# Sensor_Board.net
KiCad netlist of a schematic drawn in Altium Designer
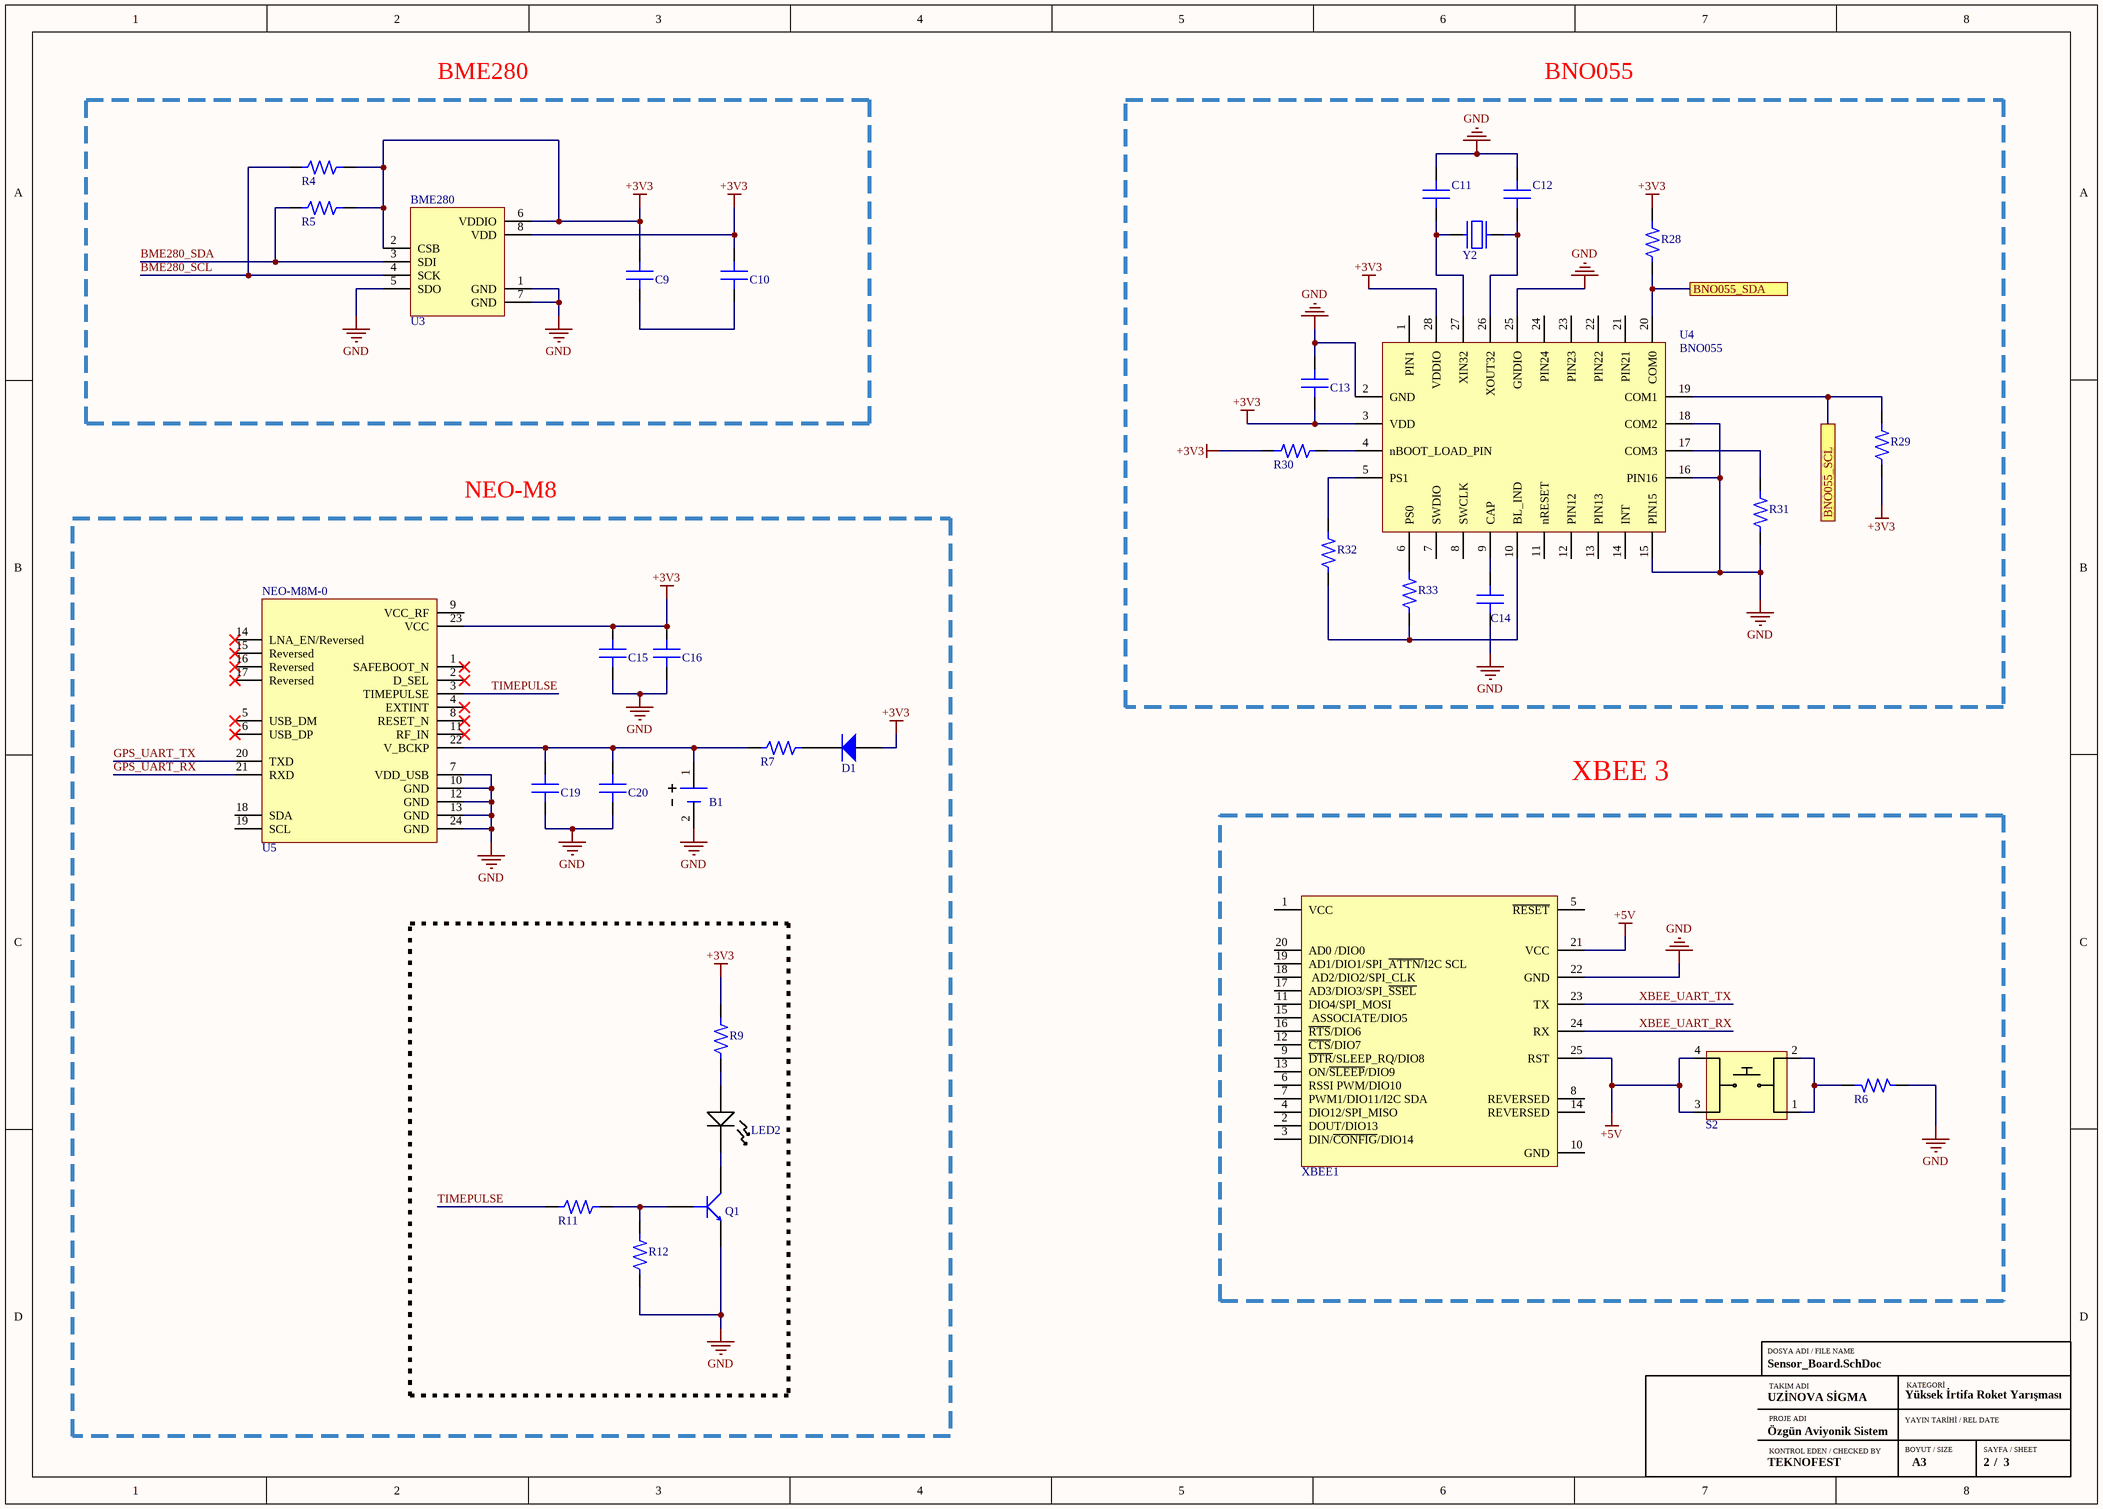
[diagram p0: Sensor_Board.SchDoc]

(export (version "E")
  (design (tool "Eeschema 10.0.6"))
  (components
    (comp (ref "B1")
      (value "MS920SE-FL27E")
      (footprint "MS920SE_Battery")
      (description "Lithium Battery Coin 3V 11mAh Rechargeable Tray")
      (fields (field (name "MANUFACTURER") "Epson") (field (name "VOLTAGE") "3V"))
      (libsource (lib "ROKET_LIBRARY") (part "BATTERY"))
    )
    (comp (ref "C9")
      (value "CAP CER 100nF 0805")
      (footprint "CAP_0805")
      (libsource (lib "ROKET_LIBRARY") (part "CAP CER 100nF 0805"))
    )
    (comp (ref "C10")
      (value "CAP CER 100nF 0805")
      (footprint "CAP_0805")
      (libsource (lib "ROKET_LIBRARY") (part "CAP CER 100nF 0805"))
    )
    (comp (ref "C11")
      (value "CAP CER 22pF 0805")
      (footprint "CAP_0805")
      (libsource (lib "Roket_Library") (part "CAP CER 22pF 0805"))
    )
    (comp (ref "C12")
      (value "CAP CER 22pF 0805")
      (footprint "CAP_0805")
      (libsource (lib "Roket_Library") (part "CAP CER 22pF 0805"))
    )
    (comp (ref "C13")
      (value "CAP CER 100nF 0805")
      (footprint "CAP_0805")
      (libsource (lib "ROKET_LIBRARY") (part "CAP CER 100nF 0805"))
    )
    (comp (ref "C14")
      (value "CAP CER 1uF 0805")
      (footprint "CAP_0805")
      (libsource (lib "ROKET_LIBRARY") (part "CAP CER 1uF 0805"))
    )
    (comp (ref "C15")
      (value "CAP CER 10uF 0805")
      (footprint "CAP_0805")
      (libsource (lib "ROKET_LIBRARY") (part "CAP CER 10uF 0805"))
    )
    (comp (ref "C16")
      (value "CAP CER 100nF 0805")
      (footprint "CAP_0805")
      (libsource (lib "ROKET_LIBRARY") (part "CAP CER 100nF 0805"))
    )
    (comp (ref "C19")
      (value "CAP CER 4.7uF 0805")
      (footprint "CAP_0805")
      (libsource (lib "ROKET_LIBRARY") (part "CAP CER 4.7uF 0805"))
    )
    (comp (ref "C20")
      (value "CAP CER 100nF 0805")
      (footprint "CAP_0805")
      (libsource (lib "ROKET_LIBRARY") (part "CAP CER 100nF 0805"))
    )
    (comp (ref "D1")
      (value "DIODE GEN PURP 75V 150MA SOD323F")
      (footprint "SOD323F")
      (description "VR=75V IF=150mA Trr=4ns P=200mW")
      (fields
        (field (name "MANUFACTURER") "ON Semiconductor / Fairchild")
        (field (name "MANUFACTURER PART NUMBER") "1N4148WS")
      )
      (libsource (lib "ROKET_LIBRARY") (part "DIODE"))
    )
    (comp (ref "LED2")
      (value "CMD17-21VRD/TR8")
      (footprint "LED RED_0805")
      (description "LED Uni-Color Red 640nm 2-Pin SMT T/R")
      (fields (field (name "MANUFACTURER") "VCC CHML"))
      (libsource (lib "ROKET_LIBRARY") (part "LED RED"))
    )
    (comp (ref "Q1")
      (value "MMBT3904-7-F")
      (footprint "SOT_23F")
      (description "NPN Ic=200mA Vceo=40V hfe=100~300 fT=310MHz P=300mW SOT-23")
      (fields (field (name "MANUFACTURER") "Diodes Zetex"))
      (libsource (lib "ROKET_LIBRARY") (part "BJT_NPN"))
    )
    (comp (ref "R4")
      (value "RES 4.7K OHM 0805")
      (footprint "RES_0805")
      (libsource (lib "ROKET_LIBRARY") (part "RES 4.7K OHM 0805"))
    )
    (comp (ref "R5")
      (value "RES 4.7K OHM 0805")
      (footprint "RES_0805")
      (libsource (lib "ROKET_LIBRARY") (part "RES 4.7K OHM 0805"))
    )
    (comp (ref "R6")
      (value "RES 10K OHM 0805")
      (footprint "RES_0805")
      (libsource (lib "ROKET_LIBRARY") (part "RES 10K OHM 0805"))
    )
    (comp (ref "R7")
      (value "RES 1K OHM 0805")
      (footprint "RES_0805")
      (libsource (lib "ROKET_LIBRARY") (part "RES 1K OHM 0805"))
    )
    (comp (ref "R9")
      (value "RES 1K OHM 0805")
      (footprint "RES_0805")
      (libsource (lib "ROKET_LIBRARY") (part "RES 1K OHM 0805"))
    )
    (comp (ref "R11")
      (value "RES 10K OHM 0805")
      (footprint "RES_0805")
      (libsource (lib "ROKET_LIBRARY") (part "RES 10K OHM 0805"))
    )
    (comp (ref "R12")
      (value "RES 10K OHM 0805")
      (footprint "RES_0805")
      (libsource (lib "ROKET_LIBRARY") (part "RES 10K OHM 0805"))
    )
    (comp (ref "R28")
      (value "RES 10K OHM 0805")
      (footprint "RES_0805")
      (libsource (lib "ROKET_LIBRARY") (part "RES 10K OHM 0805"))
    )
    (comp (ref "R29")
      (value "RES 10K OHM 0805")
      (footprint "RES_0805")
      (libsource (lib "ROKET_LIBRARY") (part "RES 10K OHM 0805"))
    )
    (comp (ref "R30")
      (value "RES 10K OHM 0805")
      (footprint "RES_0805")
      (libsource (lib "ROKET_LIBRARY") (part "RES 10K OHM 0805"))
    )
    (comp (ref "R31")
      (value "RES 10K OHM 0805")
      (footprint "RES_0805")
      (libsource (lib "ROKET_LIBRARY") (part "RES 10K OHM 0805"))
    )
    (comp (ref "R32")
      (value "RES 10K OHM 0805")
      (footprint "RES_0805")
      (libsource (lib "ROKET_LIBRARY") (part "RES 10K OHM 0805"))
    )
    (comp (ref "R33")
      (value "RES 10K OHM 0805")
      (footprint "RES_0805")
      (libsource (lib "ROKET_LIBRARY") (part "RES 10K OHM 0805"))
    )
    (comp (ref "S2")
      (value "PTS815 SJG 250 SMTR LFS")
      (footprint "BUTTON")
      (description "Switch Tactile N.O. SPST Button J-Bend 0.05A 12VDC 3.92N SMD T/R")
      (fields
        (field (name "MANUFACTURER") "ITT C&K")
        (field (name "MANUFACTURER PART NUMBER") "PTS815SJG250SMTRLFS")
      )
      (libsource (lib "ROKET_LIBRARY") (part "BUTTON"))
    )
    (comp (ref "U3")
      (value "BME280")
      (footprint "BME280")
      (description "Pressure, Temperature and Humidity Sensor Digital Output 1.8V 8-Pin LGA T/R")
      (fields (field (name "MANUFACTURER") "Bosch Tools"))
      (libsource (lib "ROKET_LIBRARY") (part "BME280"))
    )
    (comp (ref "U4")
      (value "BNO055")
      (footprint "BNO055")
      (description "BNO055 Series 1.7 to 3.6 V Intelligent 9-Axis Absolute Orientation Sensor-LGA-28")
      (fields (field (name "MANUFACTURER") "Bosch"))
      (libsource (lib "ROKET_LIBRARY") (part "BNO055"))
    )
    (comp (ref "U5")
      (value "NEO-M8M-0")
      (footprint "NEO-M8-GPS")
      (description "Rf Rcvr Gnss/gps 1.575GHZ 24LCC")
      (fields (field (name "MANUFACTURER") "u-blox"))
      (libsource (lib "ROKET_LIBRARY") (part "NEO-M8"))
    )
    (comp (ref "XBEE1")
      (value "XB3-24Z8ST-J")
      (footprint "XBEE3")
      (description "Zigbee Module, 2.4 Ghz, Sma Ant, Th Mt Rohs Compliant: Yes")
      (fields (field (name "MANUFACTURER") "Digi International"))
      (libsource (lib "Roket_Library") (part "XBEE3"))
    )
    (comp (ref "Y2")
      (value "CRYSTAL 32.7680KHZ 12.5PF SMD")
      (footprint "CRYSTAL_ABS05")
      (description "Crystal 0.032768MHz ±20ppm (Tol) 12.5pF Flexural 90000Ohm 2-Pin CSMD T/R")
      (fields
        (field (name "MANUFACTURER") "Abracon")
        (field (name "MANUFACTURER PART NUMBER") "ABS05-32.768KHZ-T")
      )
      (libsource (lib "ROKET_LIBRARY") (part "CRYSTAL"))
    )
  )
  (nets
    (net (code "1") (name "+3V3") (class "Default")
      (node (ref "C10") (pin "2") (pinfunction "2_2") (pintype "passive"))
      (node (ref "C13") (pin "1") (pinfunction "1_1") (pintype "passive"))
      (node (ref "C15") (pin "2") (pinfunction "2_2") (pintype "passive"))
      (node (ref "C16") (pin "2") (pinfunction "2_2") (pintype "passive"))
      (node (ref "C9") (pin "2") (pinfunction "2_2") (pintype "passive"))
      (node (ref "D1") (pin "2") (pinfunction "ANODE_2") (pintype "passive"))
      (node (ref "R28") (pin "2") (pinfunction "2_2") (pintype "passive"))
      (node (ref "R29") (pin "1") (pinfunction "1_1") (pintype "passive"))
      (node (ref "R30") (pin "2") (pinfunction "2_2") (pintype "passive"))
      (node (ref "R4") (pin "2") (pinfunction "2_2") (pintype "passive"))
      (node (ref "R5") (pin "2") (pinfunction "2_2") (pintype "passive"))
      (node (ref "R9") (pin "2") (pinfunction "2_2") (pintype "passive"))
      (node (ref "U3") (pin "2") (pinfunction "CSB_2") (pintype "passive"))
      (node (ref "U3") (pin "6") (pinfunction "VDDIO_6") (pintype "passive"))
      (node (ref "U3") (pin "8") (pinfunction "VDD_8") (pintype "passive"))
      (node (ref "U4") (pin "28") (pinfunction "VDDIO_28") (pintype "passive"))
      (node (ref "U4") (pin "3") (pinfunction "VDD_3") (pintype "passive"))
      (node (ref "U5") (pin "23") (pinfunction "VCC_23") (pintype "passive"))
    )
    (net (code "2") (name "+5V") (class "Default")
      (node (ref "S2") (pin "3") (pinfunction "3_3") (pintype "passive"))
      (node (ref "S2") (pin "4") (pinfunction "4_4") (pintype "passive"))
      (node (ref "XBEE1") (pin "21") (pinfunction "VCC_21") (pintype "passive"))
      (node (ref "XBEE1") (pin "25") (pinfunction "RST_25") (pintype "passive"))
    )
    (net (code "3") (name "/BME280_SCL") (class "Default")
      (node (ref "R4") (pin "1") (pinfunction "1_1") (pintype "passive"))
      (node (ref "U3") (pin "4") (pinfunction "SCK_4") (pintype "passive"))
    )
    (net (code "4") (name "/BME280_SDA") (class "Default")
      (node (ref "R5") (pin "1") (pinfunction "1_1") (pintype "passive"))
      (node (ref "U3") (pin "3") (pinfunction "SDI_3") (pintype "passive"))
    )
    (net (code "5") (name "/BNO055_SCL") (class "Default")
      (node (ref "R29") (pin "2") (pinfunction "2_2") (pintype "passive"))
      (node (ref "U4") (pin "19") (pinfunction "COM1_19") (pintype "passive"))
    )
    (net (code "6") (name "/BNO055_SDA") (class "Default")
      (node (ref "R28") (pin "1") (pinfunction "1_1") (pintype "passive"))
      (node (ref "U4") (pin "20") (pinfunction "COM0_20") (pintype "passive"))
    )
    (net (code "7") (name "/GPS_UART_RX") (class "Default")
      (node (ref "U5") (pin "21") (pinfunction "RXD_21") (pintype "passive"))
    )
    (net (code "8") (name "/GPS_UART_TX") (class "Default")
      (node (ref "U5") (pin "20") (pinfunction "TXD_20") (pintype "passive"))
    )
    (net (code "9") (name "/TIMEPULSE") (class "Default")
      (node (ref "R11") (pin "1") (pinfunction "1_1") (pintype "passive"))
      (node (ref "U5") (pin "3") (pinfunction "TIMEPULSE_3") (pintype "passive"))
    )
    (net (code "10") (name "/XBEE_UART_RX") (class "Default")
      (node (ref "XBEE1") (pin "24") (pinfunction "RX_24") (pintype "passive"))
    )
    (net (code "11") (name "/XBEE_UART_TX") (class "Default")
      (node (ref "XBEE1") (pin "23") (pinfunction "TX_23") (pintype "passive"))
    )
    (net (code "12") (name "GND") (class "Default")
      (node (ref "B1") (pin "2") (pinfunction "2_2") (pintype "passive"))
      (node (ref "C11") (pin "2") (pinfunction "2_2") (pintype "passive"))
      (node (ref "C12") (pin "2") (pinfunction "2_2") (pintype "passive"))
      (node (ref "C13") (pin "2") (pinfunction "2_2") (pintype "passive"))
      (node (ref "C14") (pin "1") (pinfunction "1_1") (pintype "passive"))
      (node (ref "C15") (pin "1") (pinfunction "1_1") (pintype "passive"))
      (node (ref "C16") (pin "1") (pinfunction "1_1") (pintype "passive"))
      (node (ref "C19") (pin "1") (pinfunction "1_1") (pintype "passive"))
      (node (ref "C20") (pin "1") (pinfunction "1_1") (pintype "passive"))
      (node (ref "Q1") (pin "2") (pinfunction "E_2") (pintype "passive"))
      (node (ref "R12") (pin "1") (pinfunction "1_1") (pintype "passive"))
      (node (ref "R31") (pin "1") (pinfunction "1_1") (pintype "passive"))
      (node (ref "R6") (pin "1") (pinfunction "1_1") (pintype "passive"))
      (node (ref "U3") (pin "1") (pinfunction "GND_1") (pintype "passive"))
      (node (ref "U3") (pin "5") (pinfunction "SDO_5") (pintype "passive"))
      (node (ref "U3") (pin "7") (pinfunction "GND_7") (pintype "passive"))
      (node (ref "U4") (pin "15") (pinfunction "PIN15_15") (pintype "passive"))
      (node (ref "U4") (pin "16") (pinfunction "PIN16_16") (pintype "passive"))
      (node (ref "U4") (pin "18") (pinfunction "COM2_18") (pintype "passive"))
      (node (ref "U4") (pin "2") (pinfunction "GND_2") (pintype "passive"))
      (node (ref "U4") (pin "25") (pinfunction "GNDIO_25") (pintype "passive"))
      (node (ref "U5") (pin "10") (pinfunction "GND_10") (pintype "passive"))
      (node (ref "U5") (pin "12") (pinfunction "GND_12") (pintype "passive"))
      (node (ref "U5") (pin "13") (pinfunction "GND_13") (pintype "passive"))
      (node (ref "U5") (pin "24") (pinfunction "GND_24") (pintype "passive"))
      (node (ref "U5") (pin "7") (pinfunction "VDD_USB_7") (pintype "passive"))
      (node (ref "XBEE1") (pin "22") (pinfunction "GND_22") (pintype "passive"))
    )
    (net (code "13") (name "Net-(C10-Pad1)") (class "Default")
      (node (ref "C10") (pin "1") (pinfunction "1_1") (pintype "passive"))
      (node (ref "C9") (pin "1") (pinfunction "1_1") (pintype "passive"))
    )
    (net (code "14") (name "Net-(D1-CATHODE)") (class "Default")
      (node (ref "D1") (pin "1") (pinfunction "CATHODE_1") (pintype "passive"))
      (node (ref "R7") (pin "2") (pinfunction "2_2") (pintype "passive"))
    )
    (net (code "15") (name "Net-(LED2-Pad1)") (class "Default")
      (node (ref "LED2") (pin "1") (pinfunction "1_1") (pintype "passive"))
      (node (ref "R9") (pin "1") (pinfunction "1_1") (pintype "passive"))
    )
    (net (code "16") (name "Net-(Q1-B)") (class "Default")
      (node (ref "Q1") (pin "1") (pinfunction "B_1") (pintype "passive"))
      (node (ref "R11") (pin "2") (pinfunction "2_2") (pintype "passive"))
      (node (ref "R12") (pin "2") (pinfunction "2_2") (pintype "passive"))
    )
    (net (code "17") (name "Net-(Q1-C)") (class "Default")
      (node (ref "LED2") (pin "2") (pinfunction "2_2") (pintype "passive"))
      (node (ref "Q1") (pin "3") (pinfunction "C_3") (pintype "passive"))
    )
    (net (code "18") (name "Net-(R6-Pad2)") (class "Default")
      (node (ref "R6") (pin "2") (pinfunction "2_2") (pintype "passive"))
      (node (ref "S2") (pin "1") (pinfunction "1_1") (pintype "passive"))
      (node (ref "S2") (pin "2") (pinfunction "2_2") (pintype "passive"))
    )
    (net (code "19") (name "Net-(U4-BL_IND)") (class "Default")
      (node (ref "R32") (pin "1") (pinfunction "1_1") (pintype "passive"))
      (node (ref "R33") (pin "1") (pinfunction "1_1") (pintype "passive"))
      (node (ref "U4") (pin "10") (pinfunction "BL_IND_10") (pintype "passive"))
    )
    (net (code "20") (name "Net-(U4-CAP)") (class "Default")
      (node (ref "C14") (pin "2") (pinfunction "2_2") (pintype "passive"))
      (node (ref "U4") (pin "9") (pinfunction "CAP_9") (pintype "passive"))
    )
    (net (code "21") (name "Net-(U4-COM3)") (class "Default")
      (node (ref "R31") (pin "2") (pinfunction "2_2") (pintype "passive"))
      (node (ref "U4") (pin "17") (pinfunction "COM3_17") (pintype "passive"))
    )
    (net (code "22") (name "Net-(U4-PS0)") (class "Default")
      (node (ref "R33") (pin "2") (pinfunction "2_2") (pintype "passive"))
      (node (ref "U4") (pin "6") (pinfunction "PS0_6") (pintype "passive"))
    )
    (net (code "23") (name "Net-(U4-PS1)") (class "Default")
      (node (ref "R32") (pin "2") (pinfunction "2_2") (pintype "passive"))
      (node (ref "U4") (pin "5") (pinfunction "PS1_5") (pintype "passive"))
    )
    (net (code "24") (name "Net-(U4-XIN32)") (class "Default")
      (node (ref "C11") (pin "1") (pinfunction "1_1") (pintype "passive"))
      (node (ref "U4") (pin "27") (pinfunction "XIN32_27") (pintype "passive"))
      (node (ref "Y2") (pin "1") (pinfunction "1_1") (pintype "passive"))
    )
    (net (code "25") (name "Net-(U4-XOUT32)") (class "Default")
      (node (ref "C12") (pin "1") (pinfunction "1_1") (pintype "passive"))
      (node (ref "U4") (pin "26") (pinfunction "XOUT32_26") (pintype "passive"))
      (node (ref "Y2") (pin "2") (pinfunction "2_2") (pintype "passive"))
    )
    (net (code "26") (name "Net-(U4-nBOOT_LOAD_PIN)") (class "Default")
      (node (ref "R30") (pin "1") (pinfunction "1_1") (pintype "passive"))
      (node (ref "U4") (pin "4") (pinfunction "nBOOT_LOAD_PIN_4") (pintype "passive"))
    )
    (net (code "27") (name "Net-(U5-V_BCKP)") (class "Default")
      (node (ref "B1") (pin "1") (pinfunction "1_1") (pintype "passive"))
      (node (ref "C19") (pin "2") (pinfunction "2_2") (pintype "passive"))
      (node (ref "C20") (pin "2") (pinfunction "2_2") (pintype "passive"))
      (node (ref "R7") (pin "1") (pinfunction "1_1") (pintype "passive"))
      (node (ref "U5") (pin "22") (pinfunction "V_BCKP_22") (pintype "passive"))
    )
    (net (code "28") (name "unconnected-(U4-INT-Pad14)") (class "Default")
      (node (ref "U4") (pin "14") (pinfunction "INT_14") (pintype "passive"))
    )
    (net (code "29") (name "unconnected-(U4-PIN1-Pad1)") (class "Default")
      (node (ref "U4") (pin "1") (pinfunction "PIN1_1") (pintype "passive"))
    )
    (net (code "30") (name "unconnected-(U4-PIN12-Pad12)") (class "Default")
      (node (ref "U4") (pin "12") (pinfunction "PIN12_12") (pintype "passive"))
    )
    (net (code "31") (name "unconnected-(U4-PIN13-Pad13)") (class "Default")
      (node (ref "U4") (pin "13") (pinfunction "PIN13_13") (pintype "passive"))
    )
    (net (code "32") (name "unconnected-(U4-PIN21-Pad21)") (class "Default")
      (node (ref "U4") (pin "21") (pinfunction "PIN21_21") (pintype "passive"))
    )
    (net (code "33") (name "unconnected-(U4-PIN22-Pad22)") (class "Default")
      (node (ref "U4") (pin "22") (pinfunction "PIN22_22") (pintype "passive"))
    )
    (net (code "34") (name "unconnected-(U4-PIN23-Pad23)") (class "Default")
      (node (ref "U4") (pin "23") (pinfunction "PIN23_23") (pintype "passive"))
    )
    (net (code "35") (name "unconnected-(U4-PIN24-Pad24)") (class "Default")
      (node (ref "U4") (pin "24") (pinfunction "PIN24_24") (pintype "passive"))
    )
    (net (code "36") (name "unconnected-(U4-SWCLK-Pad8)") (class "Default")
      (node (ref "U4") (pin "8") (pinfunction "SWCLK_8") (pintype "passive"))
    )
    (net (code "37") (name "unconnected-(U4-SWDIO-Pad7)") (class "Default")
      (node (ref "U4") (pin "7") (pinfunction "SWDIO_7") (pintype "passive"))
    )
    (net (code "38") (name "unconnected-(U4-nRESET-Pad11)") (class "Default")
      (node (ref "U4") (pin "11") (pinfunction "nRESET_11") (pintype "passive"))
    )
    (net (code "39") (name "unconnected-(U5-D_SEL-Pad2)") (class "Default")
      (node (ref "U5") (pin "2") (pinfunction "D_SEL_2") (pintype "passive+no_connect"))
    )
    (net (code "40") (name "unconnected-(U5-EXTINT-Pad4)") (class "Default")
      (node (ref "U5") (pin "4") (pinfunction "EXTINT_4") (pintype "passive+no_connect"))
    )
    (net (code "41") (name "unconnected-(U5-LNA_EN{slash}Reversed-Pad14)") (class "Default")
      (node (ref "U5") (pin "14") (pinfunction "LNA_EN/Reversed_14") (pintype "passive+no_connect"))
    )
    (net (code "42") (name "unconnected-(U5-RESET_N-Pad8)") (class "Default")
      (node (ref "U5") (pin "8") (pinfunction "RESET_N_8") (pintype "passive+no_connect"))
    )
    (net (code "43") (name "unconnected-(U5-RF_IN-Pad11)") (class "Default")
      (node (ref "U5") (pin "11") (pinfunction "RF_IN_11") (pintype "passive+no_connect"))
    )
    (net (code "44") (name "unconnected-(U5-Reversed-Pad15)") (class "Default")
      (node (ref "U5") (pin "15") (pinfunction "Reversed_15") (pintype "passive+no_connect"))
    )
    (net (code "45") (name "unconnected-(U5-Reversed-Pad16)") (class "Default")
      (node (ref "U5") (pin "16") (pinfunction "Reversed_16") (pintype "passive+no_connect"))
    )
    (net (code "46") (name "unconnected-(U5-Reversed-Pad17)") (class "Default")
      (node (ref "U5") (pin "17") (pinfunction "Reversed_17") (pintype "passive+no_connect"))
    )
    (net (code "47") (name "unconnected-(U5-SAFEBOOT_N-Pad1)") (class "Default")
      (node (ref "U5") (pin "1") (pinfunction "SAFEBOOT_N_1") (pintype "passive+no_connect"))
    )
    (net (code "48") (name "unconnected-(U5-SCL-Pad19)") (class "Default")
      (node (ref "U5") (pin "19") (pinfunction "SCL_19") (pintype "passive"))
    )
    (net (code "49") (name "unconnected-(U5-SDA-Pad18)") (class "Default")
      (node (ref "U5") (pin "18") (pinfunction "SDA_18") (pintype "passive"))
    )
    (net (code "50") (name "unconnected-(U5-USB_DM-Pad5)") (class "Default")
      (node (ref "U5") (pin "5") (pinfunction "USB_DM_5") (pintype "passive+no_connect"))
    )
    (net (code "51") (name "unconnected-(U5-USB_DP-Pad6)") (class "Default")
      (node (ref "U5") (pin "6") (pinfunction "USB_DP_6") (pintype "passive+no_connect"))
    )
    (net (code "52") (name "unconnected-(U5-VCC_RF-Pad9)") (class "Default")
      (node (ref "U5") (pin "9") (pinfunction "VCC_RF_9") (pintype "passive"))
    )
    (net (code "53") (name "unconnected-(XBEE1-AD0_{slash}DIO0-Pad20)") (class "Default")
      (node (ref "XBEE1") (pin "20") (pinfunction "AD0_/DIO0_20") (pintype "passive"))
    )
    (net (code "54") (name "unconnected-(XBEE1-AD1{slash}DIO1{slash}SPI_~{ATTN{slash}}I2C_SCL-Pad19)") (class "Default")
      (node (ref "XBEE1") (pin "19") (pinfunction "AD1/DIO1/SPI_~{ATTN/}I2C_SCL_19") (pintype "passive"))
    )
    (net (code "55") (name "unconnected-(XBEE1-AD3{slash}DIO3{slash}SPI_~{SSEL}-Pad17)") (class "Default")
      (node (ref "XBEE1") (pin "17") (pinfunction "AD3/DIO3/SPI_~{SSEL}_17") (pintype "passive"))
    )
    (net (code "56") (name "unconnected-(XBEE1-DIN{slash}~{CONFIG}{slash}DIO14-Pad3)") (class "Default")
      (node (ref "XBEE1") (pin "3") (pinfunction "DIN/~{CONFIG}/DIO14_3") (pintype "passive"))
    )
    (net (code "57") (name "unconnected-(XBEE1-DIO4{slash}SPI_MOSI-Pad11)") (class "Default")
      (node (ref "XBEE1") (pin "11") (pinfunction "DIO4/SPI_MOSI_11") (pintype "passive"))
    )
    (net (code "58") (name "unconnected-(XBEE1-DIO12{slash}SPI_MISO-Pad4)") (class "Default")
      (node (ref "XBEE1") (pin "4") (pinfunction "DIO12/SPI_MISO_4") (pintype "passive"))
    )
    (net (code "59") (name "unconnected-(XBEE1-DOUT{slash}DIO13-Pad2)") (class "Default")
      (node (ref "XBEE1") (pin "2") (pinfunction "DOUT/DIO13_2") (pintype "passive"))
    )
    (net (code "60") (name "unconnected-(XBEE1-GND-Pad10)") (class "Default")
      (node (ref "XBEE1") (pin "10") (pinfunction "GND_10") (pintype "passive"))
    )
    (net (code "61") (name "unconnected-(XBEE1-ON{slash}~{SLEEP}{slash}DIO9-Pad13)") (class "Default")
      (node (ref "XBEE1") (pin "13") (pinfunction "ON/~{SLEEP}/DIO9_13") (pintype "passive"))
    )
    (net (code "62") (name "unconnected-(XBEE1-PWM1{slash}DIO11{slash}I2C_SDA-Pad7)") (class "Default")
      (node (ref "XBEE1") (pin "7") (pinfunction "PWM1/DIO11/I2C_SDA_7") (pintype "passive"))
    )
    (net (code "63") (name "unconnected-(XBEE1-REVERSED-Pad8)") (class "Default")
      (node (ref "XBEE1") (pin "8") (pinfunction "REVERSED_8") (pintype "passive"))
    )
    (net (code "64") (name "unconnected-(XBEE1-REVERSED-Pad14)") (class "Default")
      (node (ref "XBEE1") (pin "14") (pinfunction "REVERSED_14") (pintype "passive"))
    )
    (net (code "65") (name "unconnected-(XBEE1-RSSI_PWM{slash}DIO10-Pad6)") (class "Default")
      (node (ref "XBEE1") (pin "6") (pinfunction "RSSI_PWM/DIO10_6") (pintype "passive"))
    )
    (net (code "66") (name "unconnected-(XBEE1-VCC-Pad1)") (class "Default")
      (node (ref "XBEE1") (pin "1") (pinfunction "VCC_1") (pintype "passive"))
    )
    (net (code "67") (name "unconnected-(XBEE1-_AD2{slash}DIO2{slash}SPI_CLK-Pad18)") (class "Default")
      (node (ref "XBEE1") (pin "18") (pinfunction "_AD2/DIO2/SPI_CLK_18") (pintype "passive"))
    )
    (net (code "68") (name "unconnected-(XBEE1-_ASSOCIATE{slash}DIO5-Pad15)") (class "Default")
      (node (ref "XBEE1") (pin "15") (pinfunction "_ASSOCIATE/DIO5_15") (pintype "passive"))
    )
    (net (code "69") (name "unconnected-(XBEE1-~{CTS}{slash}DIO7-Pad12)") (class "Default")
      (node (ref "XBEE1") (pin "12") (pinfunction "~{CTS}/DIO7_12") (pintype "passive"))
    )
    (net (code "70") (name "unconnected-(XBEE1-~{DTR}{slash}SLEEP_RQ{slash}DIO8-Pad9)") (class "Default")
      (node (ref "XBEE1") (pin "9") (pinfunction "~{DTR}/SLEEP_RQ/DIO8_9") (pintype "passive"))
    )
    (net (code "71") (name "unconnected-(XBEE1-~{RESET}-Pad5)") (class "Default")
      (node (ref "XBEE1") (pin "5") (pinfunction "~{RESET}_5") (pintype "passive"))
    )
    (net (code "72") (name "unconnected-(XBEE1-~{RTS}{slash}DIO6-Pad16)") (class "Default")
      (node (ref "XBEE1") (pin "16") (pinfunction "~{RTS}/DIO6_16") (pintype "passive"))
    )
  )
)
